# volt_sense.net
KiCad netlist of a schematic drawn in Altium Designer
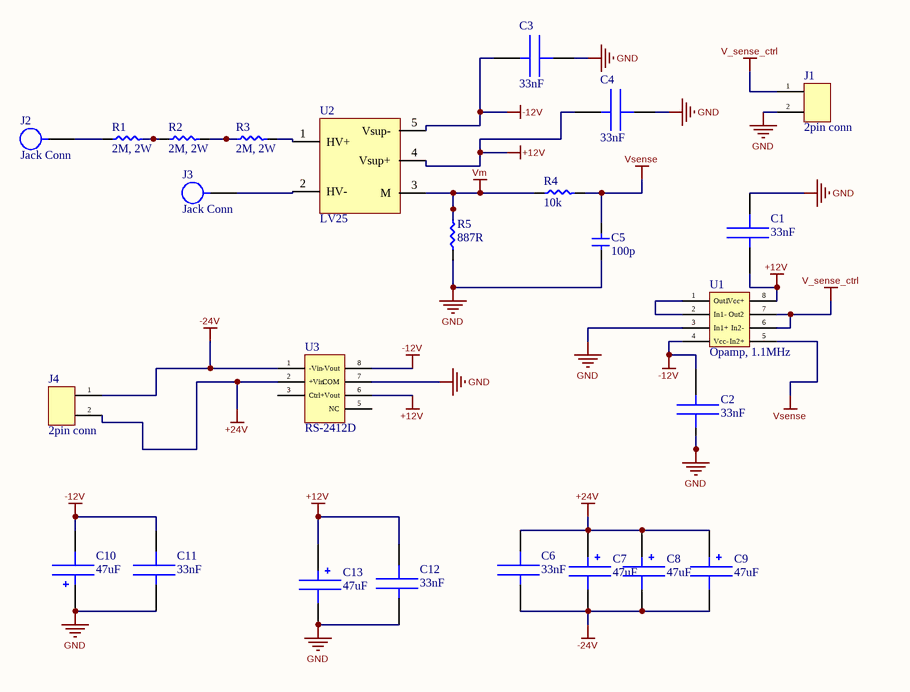
[diagram p0: volt_sense.SchDoc]

(export (version "E")
  (design (tool "Eeschema 10.0.6"))
  (components
    (comp (ref "C1")
      (value "33nF")
      (footprint "C1206")
      (description "Cap Ceramic 0.033uF 50V X7R 5% SMD 1206 125C Paper T/R")
      (fields
        (field (name "MANUFACTURER") "Samsung")
        (field (name "MANUFACTURER PART NUMBER") "CL31B333JBCNNNC")
      )
      (libsource (lib "power_ckt") (part "CL31B333JBCNNNC"))
    )
    (comp (ref "C2")
      (value "33nF")
      (footprint "C1206")
      (description "Cap Ceramic 0.033uF 50V X7R 5% SMD 1206 125C Paper T/R")
      (fields
        (field (name "MANUFACTURER") "Samsung")
        (field (name "MANUFACTURER PART NUMBER") "CL31B333JBCNNNC")
      )
      (libsource (lib "power_ckt") (part "CL31B333JBCNNNC"))
    )
    (comp (ref "C3")
      (value "33nF")
      (footprint "C1206")
      (description "Cap Ceramic 0.033uF 50V X7R 5% SMD 1206 125C Paper T/R")
      (fields
        (field (name "MANUFACTURER") "Samsung")
        (field (name "MANUFACTURER PART NUMBER") "CL31B333JBCNNNC")
      )
      (libsource (lib "power_ckt") (part "CL31B333JBCNNNC"))
    )
    (comp (ref "C4")
      (value "33nF")
      (footprint "C1206")
      (description "Cap Ceramic 0.033uF 50V X7R 5% SMD 1206 125C Paper T/R")
      (fields
        (field (name "MANUFACTURER") "Samsung")
        (field (name "MANUFACTURER PART NUMBER") "CL31B333JBCNNNC")
      )
      (libsource (lib "power_ckt") (part "CL31B333JBCNNNC"))
    )
    (comp (ref "C5")
      (value "100p")
      (footprint "C0603")
      (description "Cap Ceramic 100pF 50V X7R 10% SMD 0603 125C T/R")
      (fields
        (field (name "MANUFACTURER") "Kyocera AVX")
        (field (name "MANUFACTURER PART NUMBER") "06035C101KAT2A")
      )
      (libsource (lib "voltage_sense") (part "06035C101KAT2A"))
    )
    (comp (ref "C6")
      (value "33nF")
      (footprint "C1206")
      (description "Cap Ceramic 0.033uF 50V X7R 5% SMD 1206 125C Paper T/R")
      (fields
        (field (name "MANUFACTURER") "Samsung")
        (field (name "MANUFACTURER PART NUMBER") "CL31B333JBCNNNC")
      )
      (libsource (lib "power_ckt") (part "CL31B333JBCNNNC"))
    )
    (comp (ref "C7")
      (value "47uF")
      (footprint "CAPAE7266X82N")
      (description "Aluminum Electrolytic Capacitors - SMD 47uF 50V 105c")
      (fields
        (field (name "MANUFACTURER") "Nichicon")
        (field (name "MANUFACTURER PART NUMBER") "UCD1H470MCL1GS")
      )
      (libsource (lib "power_ckt") (part "UCD1H470MCL1GS"))
    )
    (comp (ref "C8")
      (value "47uF")
      (footprint "CAPAE7266X82N")
      (description "Aluminum Electrolytic Capacitors - SMD 47uF 50V 105c")
      (fields
        (field (name "MANUFACTURER") "Nichicon")
        (field (name "MANUFACTURER PART NUMBER") "UCD1H470MCL1GS")
      )
      (libsource (lib "power_ckt") (part "UCD1H470MCL1GS"))
    )
    (comp (ref "C9")
      (value "47uF")
      (footprint "CAPAE7266X82N")
      (description "Aluminum Electrolytic Capacitors - SMD 47uF 50V 105c")
      (fields
        (field (name "MANUFACTURER") "Nichicon")
        (field (name "MANUFACTURER PART NUMBER") "UCD1H470MCL1GS")
      )
      (libsource (lib "power_ckt") (part "UCD1H470MCL1GS"))
    )
    (comp (ref "C10")
      (value "47uF")
      (footprint "CAPAE7266X82N")
      (description "Aluminum Electrolytic Capacitors - SMD 47uF 50V 105c")
      (fields
        (field (name "MANUFACTURER") "Nichicon")
        (field (name "MANUFACTURER PART NUMBER") "UCD1H470MCL1GS")
      )
      (libsource (lib "power_ckt") (part "UCD1H470MCL1GS"))
    )
    (comp (ref "C11")
      (value "33nF")
      (footprint "C1206")
      (description "Cap Ceramic 0.033uF 50V X7R 5% SMD 1206 125C Paper T/R")
      (fields
        (field (name "MANUFACTURER") "Samsung")
        (field (name "MANUFACTURER PART NUMBER") "CL31B333JBCNNNC")
      )
      (libsource (lib "power_ckt") (part "CL31B333JBCNNNC"))
    )
    (comp (ref "C12")
      (value "33nF")
      (footprint "C1206")
      (description "Cap Ceramic 0.033uF 50V X7R 5% SMD 1206 125C Paper T/R")
      (fields
        (field (name "MANUFACTURER") "Samsung")
        (field (name "MANUFACTURER PART NUMBER") "CL31B333JBCNNNC")
      )
      (libsource (lib "power_ckt") (part "CL31B333JBCNNNC"))
    )
    (comp (ref "C13")
      (value "47uF")
      (footprint "CAPAE7266X82N")
      (description "Aluminum Electrolytic Capacitors - SMD 47uF 50V 105c")
      (fields
        (field (name "MANUFACTURER") "Nichicon")
        (field (name "MANUFACTURER PART NUMBER") "UCD1H470MCL1GS")
      )
      (libsource (lib "power_ckt") (part "UCD1H470MCL1GS"))
    )
    (comp (ref "J1")
      (value "2pin conn")
      (footprint "2pin_0.1in")
      (description "CONN HEADER VERT 2POS 2.54MM")
      (fields
        (field (name "MANUFACTURER") "TE Connectivity")
        (field (name "MANUFACTURER PART NUMBER") "640456-2")
      )
      (libsource (lib "") (part "640456-2_1"))
    )
    (comp (ref "J2")
      (value "Jack Conn")
      (footprint "575-4")
      (description "JACK NON-INSULATED .218\"")
      (fields
        (field (name "MANUFACTURER") "Keystone Electronics")
        (field (name "MANUFACTURER PART NUMBER") "575-4")
      )
      (libsource (lib "current_sense") (part "575-4"))
    )
    (comp (ref "J3")
      (value "Jack Conn")
      (footprint "575-4")
      (description "JACK NON-INSULATED .218\"")
      (fields
        (field (name "MANUFACTURER") "Keystone Electronics")
        (field (name "MANUFACTURER PART NUMBER") "575-4")
      )
      (libsource (lib "current_sense") (part "575-4"))
    )
    (comp (ref "J4")
      (value "2pin conn")
      (footprint "2pin_0.1in")
      (description "CONN HEADER VERT 2POS 2.54MM")
      (fields
        (field (name "MANUFACTURER") "TE Connectivity")
        (field (name "MANUFACTURER PART NUMBER") "640456-2")
      )
      (libsource (lib "current_sense") (part "640456-2"))
    )
    (comp (ref "R1")
      (value "2M, 2W")
      (footprint "R2512")
      (fields
        (field (name "MANUFACTURER") "TE Connectivity")
        (field (name "MANUFACTURER PART NUMBER") "SMV2W1M2JT")
      )
      (libsource (lib "voltage_sense") (part "SMV2W1M2JT"))
    )
    (comp (ref "R2")
      (value "2M, 2W")
      (footprint "R2512")
      (fields
        (field (name "MANUFACTURER") "TE Connectivity")
        (field (name "MANUFACTURER PART NUMBER") "SMV2W1M2JT")
      )
      (libsource (lib "voltage_sense") (part "SMV2W1M2JT"))
    )
    (comp (ref "R3")
      (value "2M, 2W")
      (footprint "R2512")
      (fields
        (field (name "MANUFACTURER") "TE Connectivity")
        (field (name "MANUFACTURER PART NUMBER") "SMV2W1M2JT")
      )
      (libsource (lib "voltage_sense") (part "SMV2W1M2JT"))
    )
    (comp (ref "R4")
      (value "10k")
      (footprint "R0603")
      (description "RES 10K OHM 1% 1/8W 0603")
      (fields
        (field (name "MANUFACTURER") "Stackpole Electronics")
        (field (name "MANUFACTURER PART NUMBER") "RNCP0603FTD10K0")
      )
      (libsource (lib "voltage_sense") (part "RNCP0603FTD10K0"))
    )
    (comp (ref "R5")
      (value "887R")
      (footprint "R0603")
      (description "RES SMD 887 OHM 0.1% 1/10W 0603")
      (fields
        (field (name "MANUFACTURER") "Panasonic")
        (field (name "MANUFACTURER PART NUMBER") "ERA-3AEB8870V")
      )
      (libsource (lib "voltage_sense") (part "ERA-3AEB8870V"))
    )
    (comp (ref "U1")
      (value "Opamp, 1.1MHz")
      (footprint "SO8")
      (description "IC OPAMP GP 1.1MHZ 8SO")
      (fields
        (field (name "MANUFACTURER") "STMicroelectronics")
        (field (name "MANUFACTURER PART NUMBER") "LM358DT")
      )
      (libsource (lib "current_sense") (part "LM358DT"))
    )
    (comp (ref "U2")
      (value "LV25")
      (footprint "LV25-P")
      (fields (field (name "MANUFACTURER") "LEM") (field (name "MANUFACTURER PART NUMBER") "LV25-P"))
      (libsource (lib "voltage_sense") (part "LV25-P"))
    )
    (comp (ref "U3")
      (value "RS-2412D")
      (footprint "RS2412D")
      (description "CONV DC/DC 2W DL +/-12V OUT SIP8")
      (fields (field (name "MANUFACTURER") "Recom"))
      (libsource (lib "current_sense") (part "RS-2412D"))
    )
  )
  (nets
    (net (code "1") (name "+12V") (class "Default")
      (node (ref "C1") (pin "1") (pinfunction "1_1") (pintype "power_in"))
      (node (ref "C12") (pin "2") (pinfunction "2_2") (pintype "power_in"))
      (node (ref "C13") (pin "1") (pinfunction "1_1") (pintype "power_in"))
      (node (ref "C4") (pin "1") (pinfunction "1_1") (pintype "power_in"))
      (node (ref "U1") (pin "8") (pinfunction "Vcc+_8") (pintype "power_in"))
      (node (ref "U2") (pin "4") (pinfunction "Vsup+_4") (pintype "power_in"))
      (node (ref "U3") (pin "6") (pinfunction "+Vout_6") (pintype "power_in"))
    )
    (net (code "2") (name "+24V") (class "Default")
      (node (ref "C6") (pin "2") (pinfunction "2_2") (pintype "power_in"))
      (node (ref "C7") (pin "1") (pinfunction "1_1") (pintype "power_in"))
      (node (ref "C8") (pin "1") (pinfunction "1_1") (pintype "power_in"))
      (node (ref "C9") (pin "1") (pinfunction "1_1") (pintype "power_in"))
      (node (ref "J4") (pin "2") (pinfunction "2_2") (pintype "power_in"))
      (node (ref "U3") (pin "2") (pinfunction "+Vin_2") (pintype "power_in"))
    )
    (net (code "3") (name "-12V") (class "Default")
      (node (ref "C10") (pin "2") (pinfunction "2_2") (pintype "power_in"))
      (node (ref "C11") (pin "2") (pinfunction "2_2") (pintype "power_in"))
      (node (ref "C2") (pin "1") (pinfunction "1_1") (pintype "power_in"))
      (node (ref "C3") (pin "1") (pinfunction "1_1") (pintype "power_in"))
      (node (ref "U1") (pin "4") (pinfunction "Vcc-_4") (pintype "power_in"))
      (node (ref "U2") (pin "5") (pinfunction "Vsup-_5") (pintype "power_in"))
      (node (ref "U3") (pin "8") (pinfunction "-Vout_8") (pintype "power_in"))
    )
    (net (code "4") (name "-24V") (class "Default")
      (node (ref "C6") (pin "1") (pinfunction "1_1") (pintype "power_in"))
      (node (ref "C7") (pin "2") (pinfunction "2_2") (pintype "power_in"))
      (node (ref "C8") (pin "2") (pinfunction "2_2") (pintype "power_in"))
      (node (ref "C9") (pin "2") (pinfunction "2_2") (pintype "power_in"))
      (node (ref "J4") (pin "1") (pinfunction "1_1") (pintype "power_in"))
      (node (ref "U3") (pin "1") (pinfunction "-Vin_1") (pintype "power_in"))
    )
    (net (code "5") (name "GND") (class "Default")
      (node (ref "C1") (pin "2") (pinfunction "2_2") (pintype "power_in"))
      (node (ref "C10") (pin "1") (pinfunction "1_1") (pintype "power_in"))
      (node (ref "C11") (pin "1") (pinfunction "1_1") (pintype "power_in"))
      (node (ref "C12") (pin "1") (pinfunction "1_1") (pintype "power_in"))
      (node (ref "C13") (pin "2") (pinfunction "2_2") (pintype "power_in"))
      (node (ref "C2") (pin "2") (pinfunction "2_2") (pintype "power_in"))
      (node (ref "C3") (pin "2") (pinfunction "2_2") (pintype "power_in"))
      (node (ref "C4") (pin "2") (pinfunction "2_2") (pintype "power_in"))
      (node (ref "C5") (pin "1") (pinfunction "1_1") (pintype "passive"))
      (node (ref "J1") (pin "2") (pinfunction "2_2") (pintype "power_in"))
      (node (ref "R5") (pin "1") (pinfunction "3_1") (pintype "passive"))
      (node (ref "U1") (pin "3") (pinfunction "In1+_3") (pintype "power_in"))
      (node (ref "U3") (pin "7") (pinfunction "COM_7") (pintype "power_in"))
    )
    (net (code "6") (name "Net-(R1-3)") (class "Default")
      (node (ref "J2") (pin "1") (pinfunction "1_1") (pintype "power_in"))
      (node (ref "R1") (pin "1") (pinfunction "3_1") (pintype "passive"))
    )
    (net (code "7") (name "Net-(R1-4)") (class "Default")
      (node (ref "R1") (pin "2") (pinfunction "4_2") (pintype "passive"))
      (node (ref "R2") (pin "1") (pinfunction "3_1") (pintype "passive"))
    )
    (net (code "8") (name "Net-(R2-4)") (class "Default")
      (node (ref "R2") (pin "2") (pinfunction "4_2") (pintype "passive"))
      (node (ref "R3") (pin "1") (pinfunction "3_1") (pintype "passive"))
    )
    (net (code "9") (name "Net-(R3-4)") (class "Default")
      (node (ref "R3") (pin "2") (pinfunction "4_2") (pintype "passive"))
      (node (ref "U2") (pin "1") (pinfunction "HV+_1") (pintype "power_in"))
    )
    (net (code "10") (name "Net-(U1-In1-)") (class "Default")
      (node (ref "U1") (pin "1") (pinfunction "Out1_1") (pintype "power_in"))
      (node (ref "U1") (pin "2") (pinfunction "In1-_2") (pintype "power_in"))
    )
    (net (code "11") (name "Net-(U2-HV-)") (class "Default")
      (node (ref "J3") (pin "1") (pinfunction "1_1") (pintype "power_in"))
      (node (ref "U2") (pin "2") (pinfunction "HV-_2") (pintype "power_in"))
    )
    (net (code "12") (name "V_sense_ctrl") (class "Default")
      (node (ref "J1") (pin "1") (pinfunction "1_1") (pintype "power_in"))
      (node (ref "U1") (pin "6") (pinfunction "In2-_6") (pintype "power_in"))
      (node (ref "U1") (pin "7") (pinfunction "Out2_7") (pintype "power_in"))
    )
    (net (code "13") (name "Vm") (class "Default")
      (node (ref "R4") (pin "1") (pinfunction "3_1") (pintype "passive"))
      (node (ref "R5") (pin "2") (pinfunction "4_2") (pintype "passive"))
      (node (ref "U2") (pin "3") (pinfunction "M_3") (pintype "power_in"))
    )
    (net (code "14") (name "Vsense") (class "Default")
      (node (ref "C5") (pin "2") (pinfunction "2_2") (pintype "passive"))
      (node (ref "R4") (pin "2") (pinfunction "4_2") (pintype "passive"))
      (node (ref "U1") (pin "5") (pinfunction "In2+_5") (pintype "power_in"))
    )
    (net (code "15") (name "unconnected-(U3-Ctrl-Pad3)") (class "Default")
      (node (ref "U3") (pin "3") (pinfunction "Ctrl_3") (pintype "power_in"))
    )
    (net (code "16") (name "unconnected-(U3-NC-Pad5)") (class "Default")
      (node (ref "U3") (pin "5") (pinfunction "NC_5") (pintype "power_in"))
    )
  )
)
